# SPI.net
KiCad netlist of a schematic drawn in Altium Designer
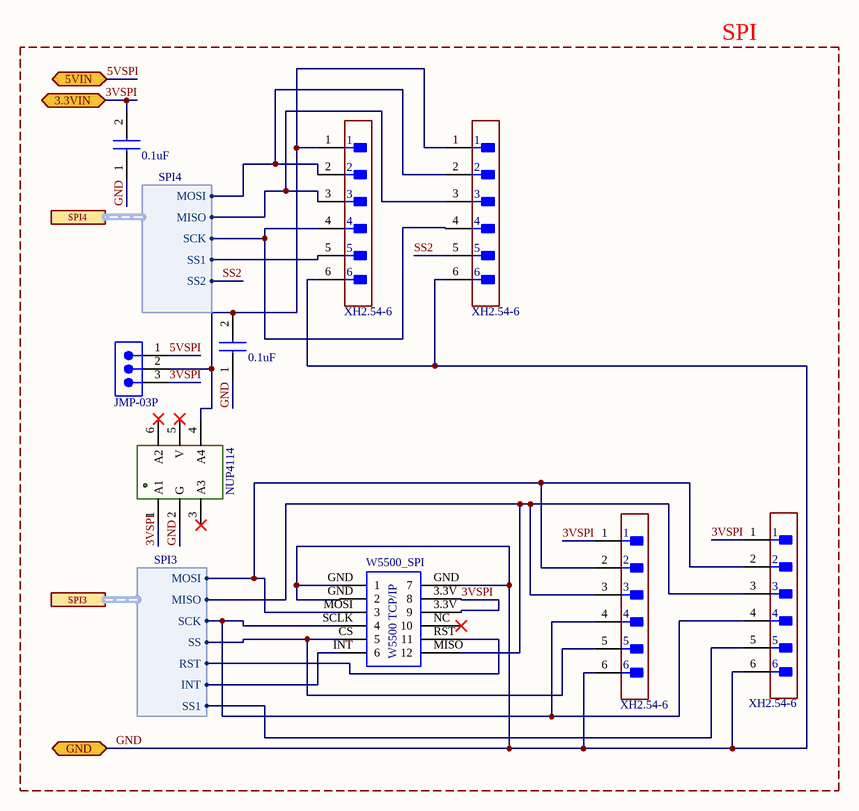
[diagram p0: SPI.SchDoc]

(export (version "E")
  (design (tool "Eeschema 10.0.6"))
  (components
    (comp (ref "CAPSPI3")
      (value "0.1uF")
      (footprint "CAP0805")
      (description "CAP-SMD0805")
      (libsource (lib "Components_Robots") (part "CAP0805"))
    )
    (comp (ref "CAPSPI4")
      (value "0.1uF")
      (footprint "CAP0805")
      (description "CAP-SMD0805")
      (libsource (lib "Components_Robots") (part "CAP0805"))
    )
    (comp (ref "JMPSPI")
      (value "JMP-03P")
      (footprint "JMP-03P")
      (description "PLS-1x3")
      (libsource (lib "Components_Robots") (part "JMP-03P"))
    )
    (comp (ref "NUPSPI")
      (value "NUP4114")
      (footprint "NUP4114")
      (description "NUP4114HMR6T1G")
      (libsource (lib "Components_Robots") (part "NUP4114"))
    )
    (comp (ref "SPI3-1")
      (value "XH2.54-6")
      (footprint "XH2.54-6")
      (description "JST XH2.54-5pin")
      (libsource (lib "Components_Robots") (part "XH2.54-6"))
    )
    (comp (ref "SPI3-2")
      (value "XH2.54-6")
      (footprint "XH2.54-6")
      (description "JST XH2.54-5pin")
      (libsource (lib "Components_Robots") (part "XH2.54-6"))
    )
    (comp (ref "SPI4-1")
      (value "XH2.54-6")
      (footprint "XH2.54-6")
      (description "JST XH2.54-5pin")
      (libsource (lib "Components_Robots") (part "XH2.54-6"))
    )
    (comp (ref "SPI4-2")
      (value "XH2.54-6")
      (footprint "XH2.54-6")
      (description "JST XH2.54-5pin")
      (libsource (lib "Components_Robots") (part "XH2.54-6"))
    )
    (comp (ref "W5500SPI")
      (value "W5500_SPI")
      (footprint "W5500")
      (description "W5500 TCP/IP")
      (libsource (lib "Components_Robots") (part "W5500"))
    )
  )
  (nets
    (net (code "3") (name "/3VSPI") (class "Default")
      (node (ref "CAPSPI3") (pin "2") (pinfunction "2_2") (pintype "passive"))
      (node (ref "JMPSPI") (pin "3") (pinfunction "3_3") (pintype "passive"))
      (node (ref "NUPSPI") (pin "1") (pinfunction "A1_1") (pintype "passive"))
      (node (ref "SPI3-1") (pin "1") (pinfunction "1_1") (pintype "passive"))
      (node (ref "SPI3-2") (pin "1") (pinfunction "1_1") (pintype "passive"))
      (node (ref "W5500SPI") (pin "3.3V") (pinfunction "8_3.3V") (pintype "passive"))
    )
    (net (code "4") (name "/5VSPI") (class "Default")
      (node (ref "JMPSPI") (pin "1") (pinfunction "1_1") (pintype "passive"))
    )
    (net (code "5") (name "/GND") (class "Default")
      (node (ref "CAPSPI3") (pin "1") (pinfunction "1_1") (pintype "passive"))
      (node (ref "CAPSPI4") (pin "1") (pinfunction "1_1") (pintype "passive"))
      (node (ref "NUPSPI") (pin "2") (pinfunction "G_2") (pintype "passive"))
      (node (ref "SPI3-1") (pin "6") (pinfunction "6_6") (pintype "passive"))
      (node (ref "SPI3-2") (pin "6") (pinfunction "6_6") (pintype "passive"))
      (node (ref "SPI4-1") (pin "6") (pinfunction "6_6") (pintype "passive"))
      (node (ref "SPI4-2") (pin "6") (pinfunction "6_6") (pintype "passive"))
      (node (ref "W5500SPI") (pin "GND") (pinfunction "1_GND") (pintype "passive"))
    )
    (net (code "6") (name "/INT") (class "Default")
      (node (ref "W5500SPI") (pin "INT") (pinfunction "6_INT") (pintype "passive"))
    )
    (net (code "7") (name "/RST") (class "Default")
      (node (ref "W5500SPI") (pin "RST") (pinfunction "11_RST") (pintype "passive"))
    )
    (net (code "8") (name "/SS") (class "Default")
      (node (ref "SPI3-1") (pin "5") (pinfunction "5_5") (pintype "passive"))
      (node (ref "W5500SPI") (pin "CS") (pinfunction "5_CS") (pintype "passive"))
    )
    (net (code "9") (name "/SS2") (class "Default")
      (node (ref "SPI4-2") (pin "5") (pinfunction "5_5") (pintype "passive"))
    )
    (net (code "12") (name "Net-(NUPSPI-A4)") (class "Default")
      (node (ref "CAPSPI4") (pin "2") (pinfunction "2_2") (pintype "passive"))
      (node (ref "JMPSPI") (pin "2") (pinfunction "2_2") (pintype "passive"))
      (node (ref "NUPSPI") (pin "4") (pinfunction "A4_4") (pintype "passive"))
      (node (ref "SPI4-1") (pin "1") (pinfunction "1_1") (pintype "passive"))
      (node (ref "SPI4-2") (pin "1") (pinfunction "1_1") (pintype "passive"))
    )
    (net (code "13") (name "Net-(SPI4-1-Pad2)") (class "Default")
      (node (ref "SPI4-1") (pin "2") (pinfunction "2_2") (pintype "passive"))
      (node (ref "SPI4-2") (pin "2") (pinfunction "2_2") (pintype "passive"))
    )
    (net (code "14") (name "Net-(SPI4-1-Pad3)") (class "Default")
      (node (ref "SPI4-1") (pin "3") (pinfunction "3_3") (pintype "passive"))
      (node (ref "SPI4-2") (pin "3") (pinfunction "3_3") (pintype "passive"))
    )
    (net (code "15") (name "Net-(SPI4-1-Pad4)") (class "Default")
      (node (ref "SPI4-1") (pin "4") (pinfunction "4_4") (pintype "passive"))
      (node (ref "SPI4-2") (pin "4") (pinfunction "4_4") (pintype "passive"))
    )
    (net (code "16") (name "Net-(W5500SPI-3)") (class "Default")
      (node (ref "SPI3-1") (pin "2") (pinfunction "2_2") (pintype "passive"))
      (node (ref "SPI3-2") (pin "2") (pinfunction "2_2") (pintype "passive"))
      (node (ref "W5500SPI") (pin "MOSI") (pinfunction "3_MOSI") (pintype "passive"))
    )
    (net (code "17") (name "Net-(W5500SPI-4)") (class "Default")
      (node (ref "SPI3-1") (pin "4") (pinfunction "4_4") (pintype "passive"))
      (node (ref "SPI3-2") (pin "4") (pinfunction "4_4") (pintype "passive"))
      (node (ref "W5500SPI") (pin "SCLK") (pinfunction "4_SCLK") (pintype "passive"))
    )
    (net (code "18") (name "Net-(W5500SPI-12)") (class "Default")
      (node (ref "SPI3-1") (pin "3") (pinfunction "3_3") (pintype "passive"))
      (node (ref "SPI3-2") (pin "3") (pinfunction "3_3") (pintype "passive"))
      (node (ref "W5500SPI") (pin "MISO") (pinfunction "12_MISO") (pintype "passive"))
    )
    (net (code "19") (name "unconnected-(NUPSPI-A2-Pad6)") (class "Default")
      (node (ref "NUPSPI") (pin "6") (pinfunction "A2_6") (pintype "passive+no_connect"))
    )
    (net (code "20") (name "unconnected-(NUPSPI-A3-Pad3)") (class "Default")
      (node (ref "NUPSPI") (pin "3") (pinfunction "A3_3") (pintype "passive+no_connect"))
    )
    (net (code "21") (name "unconnected-(NUPSPI-V-Pad5)") (class "Default")
      (node (ref "NUPSPI") (pin "5") (pinfunction "V_5") (pintype "passive+no_connect"))
    )
    (net (code "22") (name "unconnected-(SPI3-2-Pad5)") (class "Default")
      (node (ref "SPI3-2") (pin "5") (pinfunction "5_5") (pintype "passive"))
    )
    (net (code "23") (name "unconnected-(SPI4-1-Pad5)") (class "Default")
      (node (ref "SPI4-1") (pin "5") (pinfunction "5_5") (pintype "passive"))
    )
    (net (code "24") (name "unconnected-(W5500SPI-10-PadNC)") (class "Default")
      (node (ref "W5500SPI") (pin "NC") (pinfunction "10_NC") (pintype "passive+no_connect"))
    )
  )
)
